# SuperBot_Sensors.net
KiCad netlist of a schematic drawn in Altium Designer
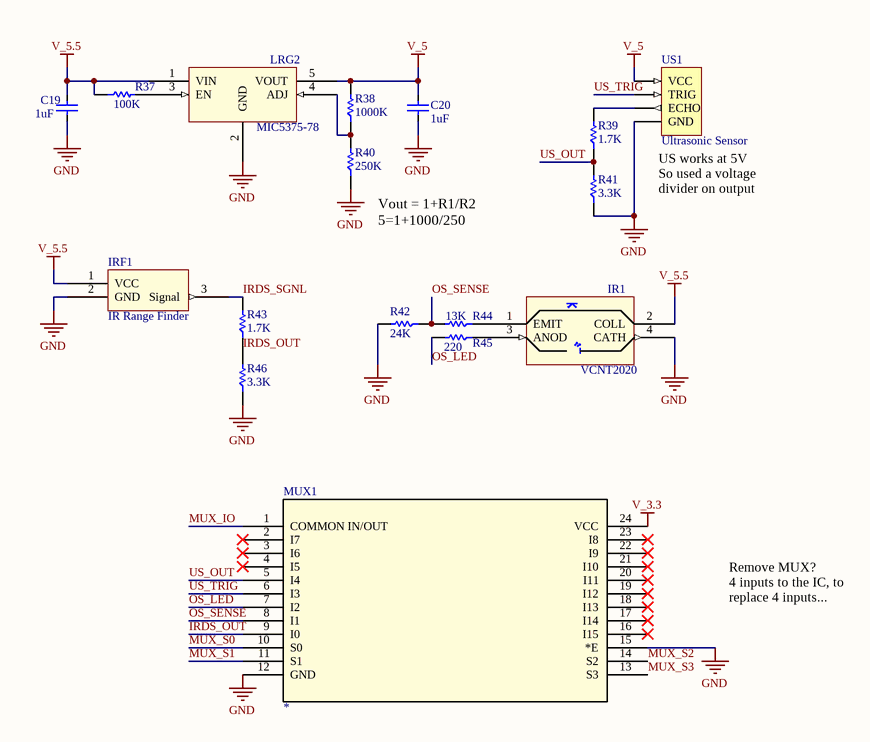
[diagram p0: SuperBot_Sensors.SchDoc]

(export (version "E")
  (design (tool "Eeschema 10.0.6"))
  (components
    (comp (ref "C19")
      (value "1uF")
      (footprint "CAP0603R")
      (description "Capacitor")
      (fields
        (field (name "MANUFACTURER") "Microchip Technology")
        (field (name "MANUFACTURER PART NUM") "MIC5378YC5-TR")
      )
      (libsource (lib "SuperBot_Schlib1") (part "C"))
    )
    (comp (ref "C20")
      (value "1uF")
      (footprint "CAP0603R")
      (description "Capacitor")
      (fields
        (field (name "MANUFACTURER") "Microchip Technology")
        (field (name "MANUFACTURER PART NUM") "MIC5378YC5-TR")
      )
      (libsource (lib "SuperBot_Schlib1") (part "C"))
    )
    (comp (ref "IR1")
      (value "VCNT2020")
      (footprint "VCNT2020")
      (description "Reflective Optical Sensor with Transistor Output")
      (fields (field (name "MANUFACTURER") "Vishay Semiconductor"))
      (libsource (lib "SuperBot_Schlib1") (part "VCNT2020"))
    )
    (comp (ref "IRF1")
      (value "IR Range Finder")
      (footprint "H3")
      (description "Sharp IR GP2Y0A21YK0F")
      (libsource (lib "SuperBot_Schlib1") (part "IR-Range-Finder"))
    )
    (comp (ref "LRG2")
      (value "MIC5375-78")
      (footprint "TSOP5_MIC537X")
      (description "Linear Voltage Regulator IC Positive Adjustable 1 Output 1.5 V ~ 4.5 V 150mA SC-70-5")
      (fields
        (field (name "MANUFACTURER") "Microchip Technology")
        (field (name "MANUFACTURER PART NUM") "MIC5378YC5-TR")
      )
      (libsource (lib "SuperBot_Schlib1") (part "MIC5378YC5"))
    )
    (comp (ref "MUX1")
      (value "*")
      (footprint "DB24-M")
      (description "Imported")
      (fields (field (name "MANUFACTURER_PART_NUMBER") "CD74HC4067SM96"))
      (libsource (lib "SuperBot_Schlib1") (part "CD74HC4067SM96"))
    )
    (comp (ref "R37")
      (value "100K")
      (footprint "RES0603R")
      (description "Resistor")
      (libsource (lib "SuperBot_Schlib1") (part "R"))
    )
    (comp (ref "R38")
      (value "1000K")
      (footprint "RES0603R")
      (description "Resistor")
      (libsource (lib "SuperBot_Schlib1") (part "R"))
    )
    (comp (ref "R39")
      (value "1.7K")
      (footprint "RES0603R")
      (description "Resistor")
      (libsource (lib "SuperBot_Schlib1") (part "R"))
    )
    (comp (ref "R40")
      (value "250K")
      (footprint "RES0603R")
      (description "Resistor")
      (libsource (lib "SuperBot_Schlib1") (part "R"))
    )
    (comp (ref "R41")
      (value "3.3K")
      (footprint "RES0603R")
      (description "Resistor")
      (libsource (lib "SuperBot_Schlib1") (part "R"))
    )
    (comp (ref "R42")
      (value "24K")
      (footprint "RES0603R")
      (description "Resistor")
      (libsource (lib "SuperBot_Schlib1") (part "R"))
    )
    (comp (ref "R43")
      (value "1.7K")
      (footprint "RES0603R")
      (description "Resistor")
      (libsource (lib "SuperBot_Schlib1") (part "R"))
    )
    (comp (ref "R44")
      (value "13K")
      (footprint "RES0603R")
      (description "Resistor")
      (libsource (lib "SuperBot_Schlib1") (part "R"))
    )
    (comp (ref "R45")
      (value "220")
      (footprint "RES0603R")
      (description "Resistor")
      (libsource (lib "SuperBot_Schlib1") (part "R"))
    )
    (comp (ref "R46")
      (value "3.3K")
      (footprint "RES0603R")
      (description "Resistor")
      (libsource (lib "SuperBot_Schlib1") (part "R"))
    )
    (comp (ref "US1")
      (value "Ultrasonic Sensor")
      (footprint "HDR1X4")
      (description "Header, 4-Pin")
      (fields (field (name "PUBLISHER") "Altium Limited"))
      (libsource (lib "Miscellaneous Connectors") (part "Header 4"))
    )
  )
  (nets
    (net (code "1") (name "/IRDS_OUT") (class "Default")
      (node (ref "MUX1") (pin "9") (pinfunction "I0_9") (pintype "passive"))
      (node (ref "R43") (pin "1") (pintype "passive"))
      (node (ref "R46") (pin "2") (pintype "passive"))
    )
    (net (code "2") (name "/IRDS_SGNL") (class "Default")
      (node (ref "IRF1") (pin "3") (pinfunction "Signal_3") (pintype "output"))
      (node (ref "R43") (pin "2") (pintype "passive"))
    )
    (net (code "3") (name "/MUX_IO") (class "Default")
      (node (ref "MUX1") (pin "1") (pinfunction "COMMON_IN/OUT_1") (pintype "passive"))
    )
    (net (code "4") (name "/MUX_S0") (class "Default")
      (node (ref "MUX1") (pin "10") (pinfunction "S0_10") (pintype "passive"))
    )
    (net (code "5") (name "/MUX_S1") (class "Default")
      (node (ref "MUX1") (pin "11") (pinfunction "S1_11") (pintype "passive"))
    )
    (net (code "6") (name "/MUX_S2") (class "Default")
      (node (ref "MUX1") (pin "14") (pinfunction "S2_14") (pintype "passive"))
    )
    (net (code "7") (name "/MUX_S3") (class "Default")
      (node (ref "MUX1") (pin "13") (pinfunction "S3_13") (pintype "passive"))
    )
    (net (code "8") (name "/OS_LED") (class "Default")
      (node (ref "MUX1") (pin "7") (pinfunction "I2_7") (pintype "passive"))
      (node (ref "R45") (pin "2") (pintype "passive"))
    )
    (net (code "9") (name "/OS_SENSE") (class "Default")
      (node (ref "MUX1") (pin "8") (pinfunction "I1_8") (pintype "passive"))
      (node (ref "R42") (pin "1") (pintype "passive"))
      (node (ref "R44") (pin "2") (pintype "passive"))
    )
    (net (code "10") (name "/US_OUT") (class "Default")
      (node (ref "MUX1") (pin "5") (pinfunction "I4_5") (pintype "passive"))
      (node (ref "R39") (pin "1") (pintype "passive"))
      (node (ref "R41") (pin "2") (pintype "passive"))
    )
    (net (code "11") (name "/US_TRIG") (class "Default")
      (node (ref "MUX1") (pin "6") (pinfunction "I3_6") (pintype "passive"))
      (node (ref "US1") (pin "2") (pinfunction "TRIG_2") (pintype "input"))
    )
    (net (code "12") (name "GND") (class "Default")
      (node (ref "C19") (pin "2") (pinfunction "2_2") (pintype "passive"))
      (node (ref "C20") (pin "1") (pinfunction "1_1") (pintype "passive"))
      (node (ref "IR1") (pin "4") (pinfunction "CATH_4") (pintype "output"))
      (node (ref "IRF1") (pin "2") (pinfunction "GND_2") (pintype "passive"))
      (node (ref "LRG2") (pin "2") (pinfunction "GND_2") (pintype "power_in"))
      (node (ref "MUX1") (pin "12") (pinfunction "GND_12") (pintype "power_in"))
      (node (ref "MUX1") (pin "15") (pinfunction "*E_15") (pintype "passive"))
      (node (ref "R40") (pin "1") (pintype "passive"))
      (node (ref "R41") (pin "1") (pintype "passive"))
      (node (ref "R42") (pin "2") (pintype "passive"))
      (node (ref "R46") (pin "1") (pintype "passive"))
      (node (ref "US1") (pin "4") (pinfunction "GND_4") (pintype "passive"))
    )
    (net (code "13") (name "Net-(IR1-ANOD)") (class "Default")
      (node (ref "IR1") (pin "3") (pinfunction "ANOD_3") (pintype "input"))
      (node (ref "R45") (pin "1") (pintype "passive"))
    )
    (net (code "14") (name "Net-(IR1-EMIT)") (class "Default")
      (node (ref "IR1") (pin "1") (pinfunction "EMIT_1") (pintype "open_emitter"))
      (node (ref "R44") (pin "1") (pintype "passive"))
    )
    (net (code "15") (name "Net-(LRG2-ADJ)") (class "Default")
      (node (ref "LRG2") (pin "4") (pinfunction "ADJ_4") (pintype "input"))
      (node (ref "R38") (pin "1") (pintype "passive"))
      (node (ref "R40") (pin "2") (pintype "passive"))
    )
    (net (code "16") (name "Net-(LRG2-EN)") (class "Default")
      (node (ref "LRG2") (pin "3") (pinfunction "EN_3") (pintype "input"))
      (node (ref "R37") (pin "2") (pintype "passive"))
    )
    (net (code "17") (name "Net-(US1-ECHO)") (class "Default")
      (node (ref "R39") (pin "2") (pintype "passive"))
      (node (ref "US1") (pin "3") (pinfunction "ECHO_3") (pintype "output"))
    )
    (net (code "18") (name "V_3.3") (class "Default")
      (node (ref "MUX1") (pin "24") (pinfunction "VCC_24") (pintype "power_in"))
    )
    (net (code "19") (name "V_5") (class "Default")
      (node (ref "C20") (pin "2") (pinfunction "2_2") (pintype "passive"))
      (node (ref "LRG2") (pin "5") (pinfunction "VOUT_5") (pintype "power_in"))
      (node (ref "R38") (pin "2") (pintype "passive"))
      (node (ref "US1") (pin "1") (pinfunction "VCC_1") (pintype "input"))
    )
    (net (code "20") (name "V_5.5") (class "Default")
      (node (ref "C19") (pin "1") (pinfunction "1_1") (pintype "passive"))
      (node (ref "IR1") (pin "2") (pinfunction "COLL_2") (pintype "open_collector"))
      (node (ref "IRF1") (pin "1") (pinfunction "VCC_1") (pintype "power_in"))
      (node (ref "LRG2") (pin "1") (pinfunction "VIN_1") (pintype "power_in"))
      (node (ref "R37") (pin "1") (pintype "passive"))
    )
    (net (code "21") (name "unconnected-(MUX1-I5-Pad4)") (class "Default")
      (node (ref "MUX1") (pin "4") (pinfunction "I5_4") (pintype "passive+no_connect"))
    )
    (net (code "22") (name "unconnected-(MUX1-I6-Pad3)") (class "Default")
      (node (ref "MUX1") (pin "3") (pinfunction "I6_3") (pintype "passive+no_connect"))
    )
    (net (code "23") (name "unconnected-(MUX1-I7-Pad2)") (class "Default")
      (node (ref "MUX1") (pin "2") (pinfunction "I7_2") (pintype "passive+no_connect"))
    )
    (net (code "24") (name "unconnected-(MUX1-I8-Pad23)") (class "Default")
      (node (ref "MUX1") (pin "23") (pinfunction "I8_23") (pintype "passive+no_connect"))
    )
    (net (code "25") (name "unconnected-(MUX1-I9-Pad22)") (class "Default")
      (node (ref "MUX1") (pin "22") (pinfunction "I9_22") (pintype "passive+no_connect"))
    )
    (net (code "26") (name "unconnected-(MUX1-I10-Pad21)") (class "Default")
      (node (ref "MUX1") (pin "21") (pinfunction "I10_21") (pintype "passive+no_connect"))
    )
    (net (code "27") (name "unconnected-(MUX1-I11-Pad20)") (class "Default")
      (node (ref "MUX1") (pin "20") (pinfunction "I11_20") (pintype "passive+no_connect"))
    )
    (net (code "28") (name "unconnected-(MUX1-I12-Pad19)") (class "Default")
      (node (ref "MUX1") (pin "19") (pinfunction "I12_19") (pintype "passive+no_connect"))
    )
    (net (code "29") (name "unconnected-(MUX1-I13-Pad18)") (class "Default")
      (node (ref "MUX1") (pin "18") (pinfunction "I13_18") (pintype "passive+no_connect"))
    )
    (net (code "30") (name "unconnected-(MUX1-I14-Pad17)") (class "Default")
      (node (ref "MUX1") (pin "17") (pinfunction "I14_17") (pintype "passive+no_connect"))
    )
    (net (code "31") (name "unconnected-(MUX1-I15-Pad16)") (class "Default")
      (node (ref "MUX1") (pin "16") (pinfunction "I15_16") (pintype "passive+no_connect"))
    )
  )
)
